# SCH.net
KiCad netlist of a schematic drawn in EAGLE
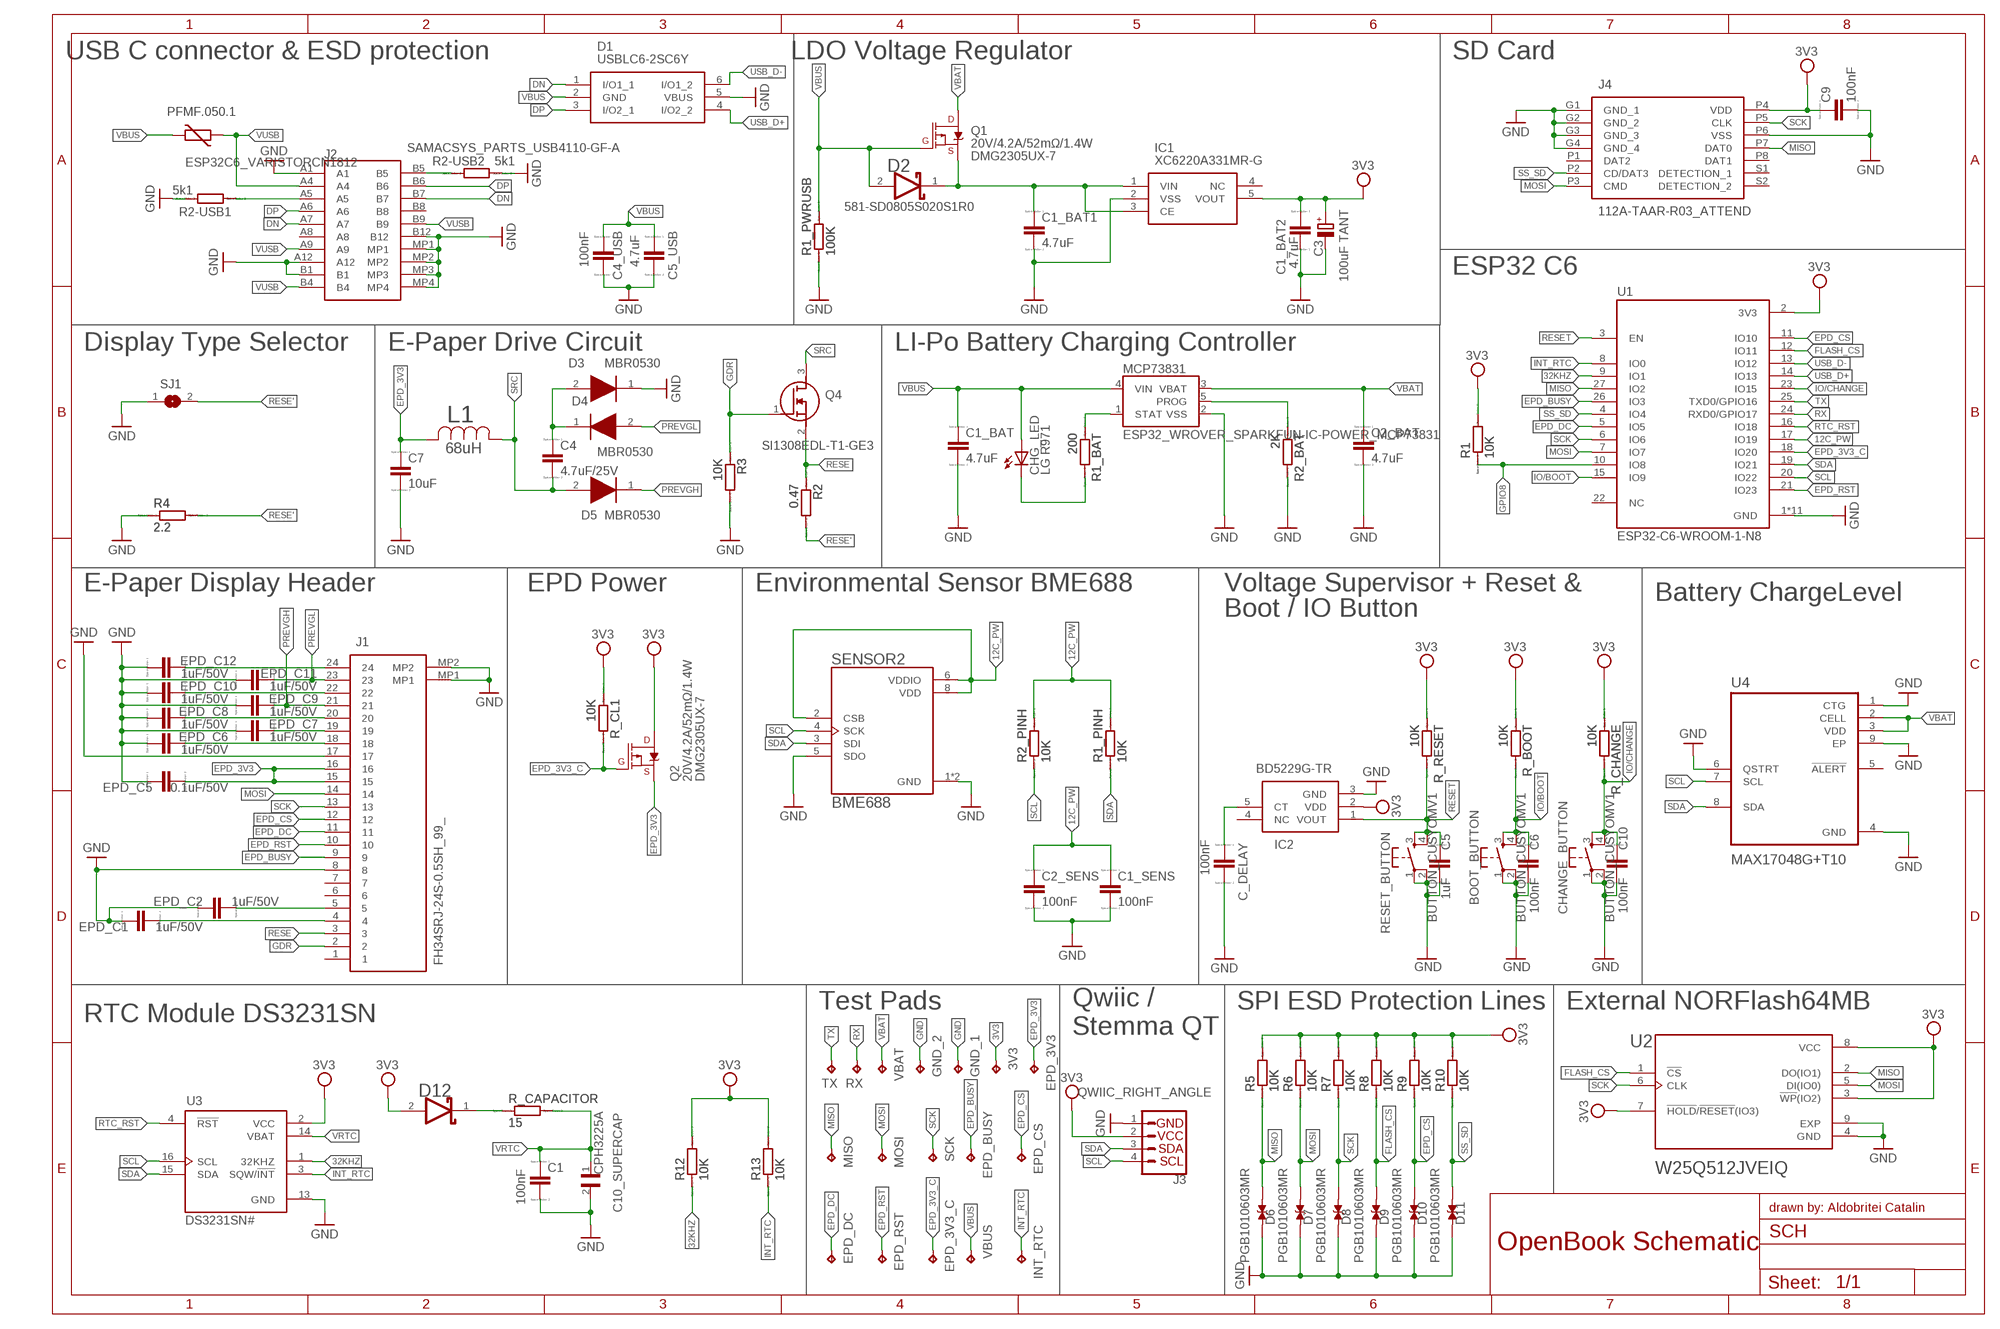
[diagram p0: schematic, sheet 1]

(export (version "E")
  (design (tool "Eeschema 10.0.6"))
  (components
    (comp (ref "3V3")
      (value "TPTP20R")
      (footprint "eagle-import:TP20R")
      (libsource (lib "eagle-import") (part "TPTP20R"))
    )
    (comp (ref "BOOT_BUTTON")
      (value "BUTTON_CUSYOMV1")
      (footprint "eagle-import:MYBUTTON")
      (libsource (lib "eagle-import") (part "BUTTON_CUSYOMV1"))
    )
    (comp (ref "C1")
      (value "100nF")
      (footprint "eagle-import:EAGLE-LTSPICE_C0402")
      (libsource (lib "eagle-import") (part "EAGLE-LTSPICE_CC0402"))
    )
    (comp (ref "C1_BAT")
      (value "4.7uF")
      (footprint "eagle-import:EAGLE-LTSPICE_C0402")
      (libsource (lib "eagle-import") (part "EAGLE-LTSPICE_CC0402"))
    )
    (comp (ref "C1_BAT1")
      (value "4.7uF")
      (footprint "eagle-import:EAGLE-LTSPICE_C0402")
      (libsource (lib "eagle-import") (part "EAGLE-LTSPICE_CC0402"))
    )
    (comp (ref "C1_BAT2")
      (value "4.7uF")
      (footprint "eagle-import:EAGLE-LTSPICE_C0402")
      (libsource (lib "eagle-import") (part "EAGLE-LTSPICE_CC0402"))
    )
    (comp (ref "C1_SENS")
      (value "100nF")
      (footprint "eagle-import:EAGLE-LTSPICE_C0402")
      (libsource (lib "eagle-import") (part "EAGLE-LTSPICE_CC0402"))
    )
    (comp (ref "C2_BAT")
      (value "4.7uF")
      (footprint "eagle-import:EAGLE-LTSPICE_C0402")
      (libsource (lib "eagle-import") (part "EAGLE-LTSPICE_CC0402"))
    )
    (comp (ref "C2_SENS")
      (value "100nF")
      (footprint "eagle-import:EAGLE-LTSPICE_C0402")
      (libsource (lib "eagle-import") (part "EAGLE-LTSPICE_CC0402"))
    )
    (comp (ref "C3")
      (value "100uF TANT")
      (footprint "eagle-import:RCL_CT3528")
      (libsource (lib "eagle-import") (part "RCL_CPOL-EUCT3528"))
    )
    (comp (ref "C4")
      (value "4.7uF/25V")
      (footprint "eagle-import:EAGLE-LTSPICE_C0402")
      (libsource (lib "eagle-import") (part "EAGLE-LTSPICE_CC0402"))
    )
    (comp (ref "C4_USB")
      (value "100nF")
      (footprint "eagle-import:EAGLE-LTSPICE_C0402")
      (libsource (lib "eagle-import") (part "EAGLE-LTSPICE_CC0402"))
    )
    (comp (ref "C5")
      (value "1uF")
      (footprint "eagle-import:EAGLE-LTSPICE_C0402")
      (libsource (lib "eagle-import") (part "EAGLE-LTSPICE_CC0402"))
    )
    (comp (ref "C5_USB")
      (value "4.7uF")
      (footprint "eagle-import:EAGLE-LTSPICE_C0402")
      (libsource (lib "eagle-import") (part "EAGLE-LTSPICE_CC0402"))
    )
    (comp (ref "C6")
      (value "100nF")
      (footprint "eagle-import:EAGLE-LTSPICE_C0402")
      (libsource (lib "eagle-import") (part "EAGLE-LTSPICE_CC0402"))
    )
    (comp (ref "C7")
      (value "10uF")
      (footprint "eagle-import:EAGLE-LTSPICE_C0402")
      (libsource (lib "eagle-import") (part "EAGLE-LTSPICE_CC0402"))
    )
    (comp (ref "C9")
      (value "100nF")
      (footprint "eagle-import:EAGLE-LTSPICE_C0402")
      (libsource (lib "eagle-import") (part "EAGLE-LTSPICE_CC0402"))
    )
    (comp (ref "C10")
      (value "100nF")
      (footprint "eagle-import:EAGLE-LTSPICE_C0402")
      (libsource (lib "eagle-import") (part "EAGLE-LTSPICE_CC0402"))
    )
    (comp (ref "C10_SUPERCAP")
      (value "CPH3225A")
      (footprint "eagle-import:CAPCP3225X100N")
      (fields (field (name "MF") "Seiko Instruments"))
      (libsource (lib "eagle-import") (part "CPH3225A"))
    )
    (comp (ref "CHANGE_BUTTON")
      (value "BUTTON_CUSYOMV1")
      (footprint "eagle-import:MYBUTTON")
      (libsource (lib "eagle-import") (part "BUTTON_CUSYOMV1"))
    )
    (comp (ref "CHG_LED")
      (value "LG R971")
      (footprint "eagle-import:ADAFRUIT_CHIP-LED0603")
      (libsource (lib "eagle-import") (part "ADAFRUIT_LEDCHIP-LED0603"))
    )
    (comp (ref "C_DELAY")
      (value "100nF")
      (footprint "eagle-import:EAGLE-LTSPICE_C0402")
      (libsource (lib "eagle-import") (part "EAGLE-LTSPICE_CC0402"))
    )
    (comp (ref "D1")
      (value "USBLC6-2SC6Y")
      (footprint "eagle-import:SOT95P280X145-6N")
      (fields (field (name "MF") "STMicroelectronics"))
      (libsource (lib "eagle-import") (part "USBLC6-2SC6Y"))
    )
    (comp (ref "D2")
      (value "ESP32_WROVER_AVX---SD0805S020S1R0_AVX_SD0805S020S1R0_0_0AVX_SD0805S020S1R0_0_0")
      (footprint "eagle-import:ESP32_WROVER_AVX---SD0805S020S1R0_AVX_SD0805S020S1R0_0")
      (fields
        (field (name "DIGIKEY_PART_NUMBER") "478-7800-1-ND")
        (field (name "MF") "AVX")
        (field (name "MOUSER_PART_NUMBER") "581-SD0805S020S1R0")
      )
      (libsource (lib "eagle-import") (part "ESP32_WROVER_AVX---SD0805S020S1R0_AVX_SD0805S020S1R0_0_0AVX_SD0805S020S1R0_0_0"))
    )
    (comp (ref "D3")
      (value "MBR0530")
      (footprint "eagle-import:SOD3716X135N")
      (fields (field (name "MF") "ON Semiconductor"))
      (libsource (lib "eagle-import") (part "MBR0530"))
    )
    (comp (ref "D4")
      (value "MBR0530")
      (footprint "eagle-import:SOD3716X135N")
      (fields (field (name "MF") "ON Semiconductor"))
      (libsource (lib "eagle-import") (part "MBR0530"))
    )
    (comp (ref "D5")
      (value "MBR0530")
      (footprint "eagle-import:SOD3716X135N")
      (fields (field (name "MF") "ON Semiconductor"))
      (libsource (lib "eagle-import") (part "MBR0530"))
    )
    (comp (ref "D6")
      (value "PGB1010603MR")
      (footprint "eagle-import:DIOC1608X36N")
      (fields (field (name "MF") "Littelfuse Inc."))
      (libsource (lib "eagle-import") (part "PGB1010603MR"))
    )
    (comp (ref "D7")
      (value "PGB1010603MR")
      (footprint "eagle-import:DIOC1608X36N")
      (fields (field (name "MF") "Littelfuse Inc."))
      (libsource (lib "eagle-import") (part "PGB1010603MR"))
    )
    (comp (ref "D8")
      (value "PGB1010603MR")
      (footprint "eagle-import:DIOC1608X36N")
      (fields (field (name "MF") "Littelfuse Inc."))
      (libsource (lib "eagle-import") (part "PGB1010603MR"))
    )
    (comp (ref "D9")
      (value "PGB1010603MR")
      (footprint "eagle-import:DIOC1608X36N")
      (fields (field (name "MF") "Littelfuse Inc."))
      (libsource (lib "eagle-import") (part "PGB1010603MR"))
    )
    (comp (ref "D10")
      (value "PGB1010603MR")
      (footprint "eagle-import:DIOC1608X36N")
      (fields (field (name "MF") "Littelfuse Inc."))
      (libsource (lib "eagle-import") (part "PGB1010603MR"))
    )
    (comp (ref "D11")
      (value "PGB1010603MR")
      (footprint "eagle-import:DIOC1608X36N")
      (fields (field (name "MF") "Littelfuse Inc."))
      (libsource (lib "eagle-import") (part "PGB1010603MR"))
    )
    (comp (ref "D12")
      (value "ESP32_WROVER_AVX---SD0805S020S1R0_AVX_SD0805S020S1R0_0_0AVX_SD0805S020S1R0_0_0")
      (footprint "eagle-import:ESP32_WROVER_AVX---SD0805S020S1R0_AVX_SD0805S020S1R0_0")
      (fields
        (field (name "DIGIKEY_PART_NUMBER") "478-7800-1-ND")
        (field (name "MF") "AVX")
        (field (name "MOUSER_PART_NUMBER") "581-SD0805S020S1R0")
      )
      (libsource (lib "eagle-import") (part "ESP32_WROVER_AVX---SD0805S020S1R0_AVX_SD0805S020S1R0_0_0AVX_SD0805S020S1R0_0_0"))
    )
    (comp (ref "EPD_3V3")
      (value "TPTP20R")
      (footprint "eagle-import:TP20R")
      (libsource (lib "eagle-import") (part "TPTP20R"))
    )
    (comp (ref "EPD_3V3_C")
      (value "TPTP20R")
      (footprint "eagle-import:TP20R")
      (libsource (lib "eagle-import") (part "TPTP20R"))
    )
    (comp (ref "EPD_BUSY")
      (value "TPTP20R")
      (footprint "eagle-import:TP20R")
      (libsource (lib "eagle-import") (part "TPTP20R"))
    )
    (comp (ref "EPD_C1")
      (value "1uF/50V")
      (footprint "eagle-import:EAGLE-LTSPICE_C0402")
      (libsource (lib "eagle-import") (part "EAGLE-LTSPICE_CC0402"))
    )
    (comp (ref "EPD_C2")
      (value "1uF/50V")
      (footprint "eagle-import:EAGLE-LTSPICE_C0402")
      (libsource (lib "eagle-import") (part "EAGLE-LTSPICE_CC0402"))
    )
    (comp (ref "EPD_C5")
      (value "0.1uF/50V")
      (footprint "eagle-import:EAGLE-LTSPICE_C0402")
      (libsource (lib "eagle-import") (part "EAGLE-LTSPICE_CC0402"))
    )
    (comp (ref "EPD_C6")
      (value "1uF/50V")
      (footprint "eagle-import:EAGLE-LTSPICE_C0402")
      (libsource (lib "eagle-import") (part "EAGLE-LTSPICE_CC0402"))
    )
    (comp (ref "EPD_C7")
      (value "1uF/50V")
      (footprint "eagle-import:EAGLE-LTSPICE_C0402")
      (libsource (lib "eagle-import") (part "EAGLE-LTSPICE_CC0402"))
    )
    (comp (ref "EPD_C8")
      (value "1uF/50V")
      (footprint "eagle-import:EAGLE-LTSPICE_C0402")
      (libsource (lib "eagle-import") (part "EAGLE-LTSPICE_CC0402"))
    )
    (comp (ref "EPD_C9")
      (value "1uF/50V")
      (footprint "eagle-import:EAGLE-LTSPICE_C0402")
      (libsource (lib "eagle-import") (part "EAGLE-LTSPICE_CC0402"))
    )
    (comp (ref "EPD_C10")
      (value "1uF/50V")
      (footprint "eagle-import:EAGLE-LTSPICE_C0402")
      (libsource (lib "eagle-import") (part "EAGLE-LTSPICE_CC0402"))
    )
    (comp (ref "EPD_C11")
      (value "1uF/50V")
      (footprint "eagle-import:EAGLE-LTSPICE_C0402")
      (libsource (lib "eagle-import") (part "EAGLE-LTSPICE_CC0402"))
    )
    (comp (ref "EPD_C12")
      (value "1uF/50V")
      (footprint "eagle-import:EAGLE-LTSPICE_C0402")
      (libsource (lib "eagle-import") (part "EAGLE-LTSPICE_CC0402"))
    )
    (comp (ref "EPD_CS")
      (value "TPTP20R")
      (footprint "eagle-import:TP20R")
      (libsource (lib "eagle-import") (part "TPTP20R"))
    )
    (comp (ref "EPD_DC")
      (value "TPTP20R")
      (footprint "eagle-import:TP20R")
      (libsource (lib "eagle-import") (part "TPTP20R"))
    )
    (comp (ref "EPD_RST")
      (value "TPTP20R")
      (footprint "eagle-import:TP20R")
      (libsource (lib "eagle-import") (part "TPTP20R"))
    )
    (comp (ref "GND_1")
      (value "TPTP20R")
      (footprint "eagle-import:TP20R")
      (libsource (lib "eagle-import") (part "TPTP20R"))
    )
    (comp (ref "GND_2")
      (value "TPTP20R")
      (footprint "eagle-import:TP20R")
      (libsource (lib "eagle-import") (part "TPTP20R"))
    )
    (comp (ref "IC1")
      (value "XC6220A331MR-G")
      (footprint "eagle-import:SOT95P280X120-5N")
      (fields (field (name "MOUSER_PART_NUMBER") "865-XC6220A331MR-G"))
      (libsource (lib "eagle-import") (part "XC6220A331MR-G"))
    )
    (comp (ref "IC2")
      (value "BD5229G-TR")
      (footprint "eagle-import:SOT95P280X125-5N")
      (fields (field (name "MOUSER_PART_NUMBER") "755-BD5229G-TR"))
      (libsource (lib "eagle-import") (part "BD5229G-TR"))
    )
    (comp (ref "INT_RTC")
      (value "TPTP20R")
      (footprint "eagle-import:TP20R")
      (libsource (lib "eagle-import") (part "TPTP20R"))
    )
    (comp (ref "J1")
      (value "FH34SRJ-24S-0.5SH_99_")
      (footprint "eagle-import:FH34SRJ24S05SH99")
      (fields
        (field (name "MANUFACTURER_PART_NUMBER") "FH34SRJ-24S-0.5SH(99)")
        (field (name "MOUSER_PART_NUMBER") "798-FH34SRJ24S05SH99")
      )
      (libsource (lib "eagle-import") (part "FH34SRJ-24S-0.5SH_99_"))
    )
    (comp (ref "J2")
      (value "SAMACSYS_PARTS_USB4110-GF-A")
      (footprint "eagle-import:SAMACSYS_PARTS_USB4110GFA")
      (fields
        (field (name "MANUFACTURER_PART_NUMBER") "USB4110-GF-A")
        (field (name "MOUSER_PART_NUMBER") "640-USB4110-GF-A")
      )
      (libsource (lib "eagle-import") (part "SAMACSYS_PARTS_USB4110-GF-A"))
    )
    (comp (ref "J3")
      (value "QWIIC_RIGHT_ANGLE")
      (footprint "eagle-import:JST04_1MM_RA")
      (libsource (lib "eagle-import") (part "QWIIC_CONNECTORJS-1MM"))
    )
    (comp (ref "J4")
      (value "112A-TAAR-R03_ATTEND")
      (footprint "eagle-import:112ATAARR03ATTEND")
      (fields (field (name "MANUFACTURER_PART_NUMBER") "112A-TAAR-R03 ATTEND"))
      (libsource (lib "eagle-import") (part "112A-TAAR-R03_ATTEND"))
    )
    (comp (ref "L1")
      (value "68uH")
      (footprint "eagle-import:IND_4828-WE-TPC_WRE")
      (fields
        (field (name "MANUFACTURER_PART_NUMBER") "744043680")
        (field (name "COPYRIGHT") "Copyright (C) 2024 Ultra Librarian. All rights reserved.")
      )
      (libsource (lib "eagle-import") (part "744043680IND_4828-WE-TPC_WRE"))
    )
    (comp (ref "MCP73831")
      (value "ESP32_WROVER_SPARKFUN-IC-POWER_MCP73831")
      (footprint "eagle-import:ESP32_WROVER_SPARKFUN-IC-POWER_SOT23-5")
      (libsource (lib "eagle-import") (part "ESP32_WROVER_SPARKFUN-IC-POWER_MCP73831"))
    )
    (comp (ref "MISO")
      (value "TPTP20R")
      (footprint "eagle-import:TP20R")
      (libsource (lib "eagle-import") (part "TPTP20R"))
    )
    (comp (ref "MOSI")
      (value "TPTP20R")
      (footprint "eagle-import:TP20R")
      (libsource (lib "eagle-import") (part "TPTP20R"))
    )
    (comp (ref "PFMF.050.1")
      (value "ESP32C6_VARISTORCN1812")
      (footprint "eagle-import:ESP32C6_VARISTOR_CT_CN1812")
      (libsource (lib "eagle-import") (part "ESP32C6_VARISTORCN1812"))
    )
    (comp (ref "Q1")
      (value "20V/4.2A/52mΩ/1.4W")
      (footprint "eagle-import:ESP32_WROVER_SPARKFUN-DISCRETESEMI_SOT23-3")
      (fields (field (name "PROD_ID") "DMG2305UX-7"))
      (libsource (lib "eagle-import") (part "ESP32_WROVER_SPARKFUN-DISCRETESEMI_MOSFET_PCH-DMG2305UX-7"))
    )
    (comp (ref "Q2")
      (value "20V/4.2A/52mΩ/1.4W")
      (footprint "eagle-import:ESP32_WROVER_SPARKFUN-DISCRETESEMI_SOT23-3")
      (fields (field (name "PROD_ID") "DMG2305UX-7"))
      (libsource (lib "eagle-import") (part "ESP32_WROVER_SPARKFUN-DISCRETESEMI_MOSFET_PCH-DMG2305UX-7"))
    )
    (comp (ref "Q4")
      (value "SI1308EDL-T1-GE3")
      (footprint "eagle-import:SOT65P210X110-3N")
      (fields (field (name "MF") "Vishay Siliconix"))
      (libsource (lib "eagle-import") (part "SI1308EDL-T1-GE3"))
    )
    (comp (ref "R1")
      (value "10K")
      (footprint "eagle-import:ESP32_WROVER_EAGLE-LTSPICE_R0402")
      (libsource (lib "eagle-import") (part "ESP32_WROVER_EAGLE-LTSPICE_RR0402"))
    )
    (comp (ref "R1_BAT")
      (value "200")
      (footprint "eagle-import:ESP32_WROVER_EAGLE-LTSPICE_R0402")
      (libsource (lib "eagle-import") (part "ESP32_WROVER_EAGLE-LTSPICE_RR0402"))
    )
    (comp (ref "R1_PINH")
      (value "10K")
      (footprint "eagle-import:ESP32_WROVER_EAGLE-LTSPICE_R0402")
      (libsource (lib "eagle-import") (part "ESP32_WROVER_EAGLE-LTSPICE_RR0402"))
    )
    (comp (ref "R1_PWRUSB")
      (value "100K")
      (footprint "eagle-import:ESP32_WROVER_EAGLE-LTSPICE_R0402")
      (libsource (lib "eagle-import") (part "ESP32_WROVER_EAGLE-LTSPICE_RR0402"))
    )
    (comp (ref "R2")
      (value "0.47")
      (footprint "eagle-import:ESP32_WROVER_EAGLE-LTSPICE_R0402")
      (libsource (lib "eagle-import") (part "ESP32_WROVER_EAGLE-LTSPICE_RR0402"))
    )
    (comp (ref "R2-USB1")
      (value "5k1")
      (footprint "eagle-import:ESP32_WROVER_EAGLE-LTSPICE_R0402")
      (libsource (lib "eagle-import") (part "ESP32_WROVER_EAGLE-LTSPICE_RR0402"))
    )
    (comp (ref "R2-USB2")
      (value "5k1")
      (footprint "eagle-import:ESP32_WROVER_EAGLE-LTSPICE_R0402")
      (libsource (lib "eagle-import") (part "ESP32_WROVER_EAGLE-LTSPICE_RR0402"))
    )
    (comp (ref "R2_BAT")
      (value "2K")
      (footprint "eagle-import:ESP32_WROVER_EAGLE-LTSPICE_R0402")
      (libsource (lib "eagle-import") (part "ESP32_WROVER_EAGLE-LTSPICE_RR0402"))
    )
    (comp (ref "R2_PINH")
      (value "10K")
      (footprint "eagle-import:ESP32_WROVER_EAGLE-LTSPICE_R0402")
      (libsource (lib "eagle-import") (part "ESP32_WROVER_EAGLE-LTSPICE_RR0402"))
    )
    (comp (ref "R3")
      (value "10K")
      (footprint "eagle-import:ESP32_WROVER_EAGLE-LTSPICE_R0402")
      (libsource (lib "eagle-import") (part "ESP32_WROVER_EAGLE-LTSPICE_RR0402"))
    )
    (comp (ref "R4")
      (value "2.2")
      (footprint "eagle-import:ESP32_WROVER_EAGLE-LTSPICE_R0402")
      (libsource (lib "eagle-import") (part "ESP32_WROVER_EAGLE-LTSPICE_RR0402"))
    )
    (comp (ref "R5")
      (value "10K")
      (footprint "eagle-import:ESP32_WROVER_EAGLE-LTSPICE_R0402")
      (libsource (lib "eagle-import") (part "ESP32_WROVER_EAGLE-LTSPICE_RR0402"))
    )
    (comp (ref "R6")
      (value "10K")
      (footprint "eagle-import:ESP32_WROVER_EAGLE-LTSPICE_R0402")
      (libsource (lib "eagle-import") (part "ESP32_WROVER_EAGLE-LTSPICE_RR0402"))
    )
    (comp (ref "R7")
      (value "10K")
      (footprint "eagle-import:ESP32_WROVER_EAGLE-LTSPICE_R0402")
      (libsource (lib "eagle-import") (part "ESP32_WROVER_EAGLE-LTSPICE_RR0402"))
    )
    (comp (ref "R8")
      (value "10K")
      (footprint "eagle-import:ESP32_WROVER_EAGLE-LTSPICE_R0402")
      (libsource (lib "eagle-import") (part "ESP32_WROVER_EAGLE-LTSPICE_RR0402"))
    )
    (comp (ref "R9")
      (value "10K")
      (footprint "eagle-import:ESP32_WROVER_EAGLE-LTSPICE_R0402")
      (libsource (lib "eagle-import") (part "ESP32_WROVER_EAGLE-LTSPICE_RR0402"))
    )
    (comp (ref "R10")
      (value "10K")
      (footprint "eagle-import:ESP32_WROVER_EAGLE-LTSPICE_R0402")
      (libsource (lib "eagle-import") (part "ESP32_WROVER_EAGLE-LTSPICE_RR0402"))
    )
    (comp (ref "R12")
      (value "10K")
      (footprint "eagle-import:ESP32_WROVER_EAGLE-LTSPICE_R0402")
      (libsource (lib "eagle-import") (part "ESP32_WROVER_EAGLE-LTSPICE_RR0402"))
    )
    (comp (ref "R13")
      (value "10K")
      (footprint "eagle-import:ESP32_WROVER_EAGLE-LTSPICE_R0402")
      (libsource (lib "eagle-import") (part "ESP32_WROVER_EAGLE-LTSPICE_RR0402"))
    )
    (comp (ref "RESET_BUTTON")
      (value "BUTTON_CUSYOMV1")
      (footprint "eagle-import:MYBUTTON")
      (libsource (lib "eagle-import") (part "BUTTON_CUSYOMV1"))
    )
    (comp (ref "RX")
      (value "TPTP20R")
      (footprint "eagle-import:TP20R")
      (libsource (lib "eagle-import") (part "TPTP20R"))
    )
    (comp (ref "R_BOOT")
      (value "10K")
      (footprint "eagle-import:ESP32_WROVER_EAGLE-LTSPICE_R0402")
      (libsource (lib "eagle-import") (part "ESP32_WROVER_EAGLE-LTSPICE_RR0402"))
    )
    (comp (ref "R_CAPACITOR")
      (value "15")
      (footprint "eagle-import:ESP32_WROVER_EAGLE-LTSPICE_R0402")
      (libsource (lib "eagle-import") (part "ESP32_WROVER_EAGLE-LTSPICE_RR0402"))
    )
    (comp (ref "R_CHANGE")
      (value "10K")
      (footprint "eagle-import:ESP32_WROVER_EAGLE-LTSPICE_R0402")
      (libsource (lib "eagle-import") (part "ESP32_WROVER_EAGLE-LTSPICE_RR0402"))
    )
    (comp (ref "R_CL1")
      (value "10K")
      (footprint "eagle-import:ESP32_WROVER_EAGLE-LTSPICE_R0402")
      (libsource (lib "eagle-import") (part "ESP32_WROVER_EAGLE-LTSPICE_RR0402"))
    )
    (comp (ref "R_RESET")
      (value "10K")
      (footprint "eagle-import:ESP32_WROVER_EAGLE-LTSPICE_R0402")
      (libsource (lib "eagle-import") (part "ESP32_WROVER_EAGLE-LTSPICE_RR0402"))
    )
    (comp (ref "SCK")
      (value "TPTP20R")
      (footprint "eagle-import:TP20R")
      (libsource (lib "eagle-import") (part "TPTP20R"))
    )
    (comp (ref "SENSOR2")
      (value "BME688")
      (footprint "eagle-import:ESP32_WROVER_BME680_PSON80P300X300X100-8N")
      (fields (field (name "MF") "Bosch Sensortec") (field (name "MP") "BME680"))
      (libsource (lib "eagle-import") (part "ESP32_WROVER_BME680_BME680"))
    )
    (comp (ref "SJ1") (value "SJ") (footprint "eagle-import:SJ") (libsource (lib "eagle-import") (part "SJ")))
    (comp (ref "TX")
      (value "TPTP20R")
      (footprint "eagle-import:TP20R")
      (libsource (lib "eagle-import") (part "TPTP20R"))
    )
    (comp (ref "U1")
      (value "ESP32-C6-WROOM-1-N8")
      (footprint "eagle-import:XCVR_ESP32-C6-WROOM-1-N8")
      (fields (field (name "MF") "Espressif Systems"))
      (libsource (lib "eagle-import") (part "ESP32-C6-WROOM-1-N8"))
    )
    (comp (ref "U2")
      (value "W25Q512JVEIQ")
      (footprint "eagle-import:SON127P600X800X80-9N")
      (fields (field (name "MF") "Winbond Electronics"))
      (libsource (lib "eagle-import") (part "W25Q512JVEIQ"))
    )
    (comp (ref "U3")
      (value "DS3231SN#")
      (footprint "eagle-import:SOIC127P1032X265-16N")
      (fields (field (name "MF") "Analog Devices"))
      (libsource (lib "eagle-import") (part "DS3231SN#"))
    )
    (comp (ref "U4")
      (value "MAX17048G+T10")
      (footprint "eagle-import:SON50P200X200X80-9N")
      (fields (field (name "MF") "Analog Devices"))
      (libsource (lib "eagle-import") (part "MAX17048G+T10"))
    )
    (comp (ref "VBAT")
      (value "TPTP20R")
      (footprint "eagle-import:TP20R")
      (libsource (lib "eagle-import") (part "TPTP20R"))
    )
    (comp (ref "VBUS")
      (value "TPTP20R")
      (footprint "eagle-import:TP20R")
      (libsource (lib "eagle-import") (part "TPTP20R"))
    )
  )
  (nets
    (net (code "1") (name "3V3") (class "Default")
      (node (ref "3V3") (pin "TP") (pinfunction "TP_TP") (pintype "input"))
      (node (ref "C1_BAT2") (pin "2") (pinfunction "2_2") (pintype "passive"))
      (node (ref "C3") (pin "+") (pinfunction "+_+") (pintype "passive"))
      (node (ref "C9") (pin "1") (pinfunction "1_1") (pintype "passive"))
      (node (ref "D12") (pin "2") (pinfunction "ANODE_2") (pintype "bidirectional"))
      (node (ref "IC1") (pin "5") (pinfunction "VOUT_5") (pintype "bidirectional"))
      (node (ref "IC2") (pin "2") (pinfunction "VDD_2") (pintype "bidirectional"))
      (node (ref "J3") (pin "2") (pinfunction "2_2") (pintype "power_in"))
      (node (ref "J4") (pin "P4") (pinfunction "VDD_P4") (pintype "bidirectional"))
      (node (ref "Q2") (pin "3") (pinfunction "D_3") (pintype "bidirectional"))
      (node (ref "R1") (pin "2") (pinfunction "2_2") (pintype "passive"))
      (node (ref "R10") (pin "2") (pinfunction "2_2") (pintype "passive"))
      (node (ref "R12") (pin "2") (pinfunction "2_2") (pintype "passive"))
      (node (ref "R13") (pin "2") (pinfunction "2_2") (pintype "passive"))
      (node (ref "R5") (pin "2") (pinfunction "2_2") (pintype "passive"))
      (node (ref "R6") (pin "2") (pinfunction "2_2") (pintype "passive"))
      (node (ref "R7") (pin "2") (pinfunction "2_2") (pintype "passive"))
      (node (ref "R8") (pin "2") (pinfunction "2_2") (pintype "passive"))
      (node (ref "R9") (pin "2") (pinfunction "2_2") (pintype "passive"))
      (node (ref "R_BOOT") (pin "1") (pinfunction "1_1") (pintype "passive"))
      (node (ref "R_CHANGE") (pin "1") (pinfunction "1_1") (pintype "passive"))
      (node (ref "R_CL1") (pin "1") (pinfunction "1_1") (pintype "passive"))
      (node (ref "R_RESET") (pin "1") (pinfunction "1_1") (pintype "passive"))
      (node (ref "U1") (pin "2") (pinfunction "3V3_2") (pintype "power_in"))
      (node (ref "U2") (pin "3") (pinfunction "~{WP}(IO2)_3") (pintype "bidirectional"))
      (node (ref "U2") (pin "7") (pinfunction "~{HOLD}/~{RESET}(IO3)_7") (pintype "bidirectional"))
      (node (ref "U2") (pin "8") (pinfunction "VCC_8") (pintype "power_in"))
      (node (ref "U3") (pin "2") (pinfunction "VCC_2") (pintype "power_in"))
    )
    (net (code "2") (name "12C_PW") (class "Default")
      (node (ref "C1_SENS") (pin "1") (pinfunction "1_1") (pintype "passive"))
      (node (ref "C2_SENS") (pin "1") (pinfunction "1_1") (pintype "passive"))
      (node (ref "R1_PINH") (pin "2") (pinfunction "2_2") (pintype "passive"))
      (node (ref "R2_PINH") (pin "2") (pinfunction "2_2") (pintype "passive"))
      (node (ref "SENSOR2") (pin "2") (pinfunction "CSB_2") (pintype "input"))
      (node (ref "SENSOR2") (pin "6") (pinfunction "VDDIO_6") (pintype "power_in"))
      (node (ref "SENSOR2") (pin "8") (pinfunction "VDD_8") (pintype "power_in"))
      (node (ref "U1") (pin "17") (pinfunction "IO19_17") (pintype "bidirectional"))
    )
    (net (code "3") (name "32KHZ") (class "Default")
      (node (ref "R12") (pin "1") (pinfunction "1_1") (pintype "passive"))
      (node (ref "U1") (pin "9") (pinfunction "IO1_9") (pintype "bidirectional"))
      (node (ref "U3") (pin "1") (pinfunction "32KHZ_1") (pintype "output"))
    )
    (net (code "4") (name "DN") (class "Default")
      (node (ref "D1") (pin "1") (pinfunction "I/O1_1_1") (pintype "bidirectional"))
      (node (ref "J2") (pin "A7") (pinfunction "A7_A7") (pintype "bidirectional"))
      (node (ref "J2") (pin "B7") (pinfunction "B7_B7") (pintype "bidirectional"))
    )
    (net (code "5") (name "DP") (class "Default")
      (node (ref "D1") (pin "3") (pinfunction "I/O2_1_3") (pintype "bidirectional"))
      (node (ref "J2") (pin "A6") (pinfunction "A6_A6") (pintype "bidirectional"))
      (node (ref "J2") (pin "B6") (pinfunction "B6_B6") (pintype "bidirectional"))
    )
    (net (code "6") (name "EPD_3V3") (class "Default")
      (node (ref "C7") (pin "1") (pinfunction "1_1") (pintype "passive"))
      (node (ref "EPD_3V3") (pin "TP") (pinfunction "TP_TP") (pintype "input"))
      (node (ref "EPD_C5") (pin "2") (pinfunction "2_2") (pintype "passive"))
      (node (ref "J1") (pin "15") (pinfunction "15_15") (pintype "bidirectional"))
      (node (ref "J1") (pin "16") (pinfunction "16_16") (pintype "bidirectional"))
      (node (ref "L1") (pin "2") (pinfunction "2_2") (pintype "passive"))
      (node (ref "Q2") (pin "2") (pinfunction "S_2") (pintype "bidirectional"))
    )
    (net (code "7") (name "EPD_3V3_C") (class "Default")
      (node (ref "EPD_3V3_C") (pin "TP") (pinfunction "TP_TP") (pintype "input"))
      (node (ref "Q2") (pin "1") (pinfunction "G_1") (pintype "bidirectional"))
      (node (ref "R_CL1") (pin "2") (pinfunction "2_2") (pintype "passive"))
      (node (ref "U1") (pin "18") (pinfunction "IO20_18") (pintype "bidirectional"))
    )
    (net (code "8") (name "EPD_BUSY") (class "Default")
      (node (ref "EPD_BUSY") (pin "TP") (pinfunction "TP_TP") (pintype "input"))
      (node (ref "J1") (pin "9") (pinfunction "9_9") (pintype "bidirectional"))
      (node (ref "U1") (pin "26") (pinfunction "IO3_26") (pintype "bidirectional"))
    )
    (net (code "9") (name "EPD_CS") (class "Default")
      (node (ref "D10") (pin "2") (pinfunction "2_2") (pintype "passive"))
      (node (ref "EPD_CS") (pin "TP") (pinfunction "TP_TP") (pintype "input"))
      (node (ref "J1") (pin "12") (pinfunction "12_12") (pintype "bidirectional"))
      (node (ref "R9") (pin "1") (pinfunction "1_1") (pintype "passive"))
      (node (ref "U1") (pin "11") (pinfunction "IO10_11") (pintype "bidirectional"))
    )
    (net (code "10") (name "EPD_DC") (class "Default")
      (node (ref "EPD_DC") (pin "TP") (pinfunction "TP_TP") (pintype "input"))
      (node (ref "J1") (pin "11") (pinfunction "11_11") (pintype "bidirectional"))
      (node (ref "U1") (pin "5") (pinfunction "IO5_5") (pintype "bidirectional"))
    )
    (net (code "11") (name "EPD_RST") (class "Default")
      (node (ref "EPD_RST") (pin "TP") (pinfunction "TP_TP") (pintype "input"))
      (node (ref "J1") (pin "10") (pinfunction "10_10") (pintype "bidirectional"))
      (node (ref "U1") (pin "21") (pinfunction "IO23_21") (pintype "bidirectional"))
    )
    (net (code "12") (name "FLASH_CS") (class "Default")
      (node (ref "D9") (pin "2") (pinfunction "2_2") (pintype "passive"))
      (node (ref "R8") (pin "1") (pinfunction "1_1") (pintype "passive"))
      (node (ref "U1") (pin "12") (pinfunction "IO11_12") (pintype "bidirectional"))
      (node (ref "U2") (pin "1") (pinfunction "~{CS}_1") (pintype "input"))
    )
    (net (code "13") (name "GDR") (class "Default")
      (node (ref "J1") (pin "2") (pinfunction "2_2") (pintype "bidirectional"))
      (node (ref "Q4") (pin "1") (pinfunction "G_1") (pintype "bidirectional"))
      (node (ref "R3") (pin "1") (pinfunction "1_1") (pintype "passive"))
    )
    (net (code "14") (name "GND") (class "Default")
      (node (ref "BOOT_BUTTON") (pin "1") (pinfunction "1_1") (pintype "passive"))
      (node (ref "BOOT_BUTTON") (pin "2") (pinfunction "2_2") (pintype "passive"))
      (node (ref "C1") (pin "2") (pinfunction "2_2") (pintype "passive"))
      (node (ref "C10") (pin "2") (pinfunction "2_2") (pintype "passive"))
      (node (ref "C10_SUPERCAP") (pin "2") (pinfunction "2_2") (pintype "passive"))
      (node (ref "C1_BAT") (pin "2") (pinfunction "2_2") (pintype "passive"))
      (node (ref "C1_BAT1") (pin "2") (pinfunction "2_2") (pintype "passive"))
      (node (ref "C1_BAT2") (pin "1") (pinfunction "1_1") (pintype "passive"))
      (node (ref "C1_SENS") (pin "2") (pinfunction "2_2") (pintype "passive"))
      (node (ref "C2_BAT") (pin "2") (pinfunction "2_2") (pintype "passive"))
      (node (ref "C2_SENS") (pin "2") (pinfunction "2_2") (pintype "passive"))
      (node (ref "C3") (pin "-") (pinfunction "-_-") (pintype "passive"))
      (node (ref "C4_USB") (pin "2") (pinfunction "2_2") (pintype "passive"))
      (node (ref "C5") (pin "2") (pinfunction "2_2") (pintype "passive"))
      (node (ref "C5_USB") (pin "2") (pinfunction "2_2") (pintype "passive"))
      (node (ref "C6") (pin "2") (pinfunction "2_2") (pintype "passive"))
      (node (ref "C7") (pin "2") (pinfunction "2_2") (pintype "passive"))
      (node (ref "C9") (pin "2") (pinfunction "2_2") (pintype "passive"))
      (node (ref "CHANGE_BUTTON") (pin "1") (pinfunction "1_1") (pintype "passive"))
      (node (ref "CHANGE_BUTTON") (pin "2") (pinfunction "2_2") (pintype "passive"))
      (node (ref "C_DELAY") (pin "2") (pinfunction "2_2") (pintype "passive"))
      (node (ref "D1") (pin "5") (pinfunction "VBUS_5") (pintype "bidirectional"))
      (node (ref "D10") (pin "1") (pinfunction "1_1") (pintype "passive"))
      (node (ref "D11") (pin "1") (pinfunction "1_1") (pintype "passive"))
      (node (ref "D3") (pin "1") (pinfunction "K_1") (pintype "bidirectional"))
      (node (ref "D6") (pin "1") (pinfunction "1_1") (pintype "passive"))
      (node (ref "D7") (pin "1") (pinfunction "1_1") (pintype "passive"))
      (node (ref "D8") (pin "1") (pinfunction "1_1") (pintype "passive"))
      (node (ref "D9") (pin "1") (pinfunction "1_1") (pintype "passive"))
      (node (ref "EPD_C1") (pin "1") (pinfunction "1_1") (pintype "passive"))
      (node (ref "EPD_C10") (pin "1") (pinfunction "1_1") (pintype "passive"))
      (node (ref "EPD_C11") (pin "1") (pinfunction "1_1") (pintype "passive"))
      (node (ref "EPD_C12") (pin "1") (pinfunction "1_1") (pintype "passive"))
      (node (ref "EPD_C2") (pin "1") (pinfunction "1_1") (pintype "passive"))
      (node (ref "EPD_C5") (pin "1") (pinfunction "1_1") (pintype "passive"))
      (node (ref "EPD_C6") (pin "1") (pinfunction "1_1") (pintype "passive"))
      (node (ref "EPD_C7") (pin "1") (pinfunction "1_1") (pintype "passive"))
      (node (ref "EPD_C8") (pin "1") (pinfunction "1_1") (pintype "passive"))
      (node (ref "EPD_C9") (pin "1") (pinfunction "1_1") (pintype "passive"))
      (node (ref "GND_1") (pin "TP") (pinfunction "TP_TP") (pintype "input"))
      (node (ref "GND_2") (pin "TP") (pinfunction "TP_TP") (pintype "input"))
      (node (ref "IC1") (pin "2") (pinfunction "VSS_2") (pintype "bidirectional"))
      (node (ref "IC2") (pin "3") (pinfunction "GND_3") (pintype "bidirectional"))
      (node (ref "J1") (pin "17") (pinfunction "17_17") (pintype "bidirectional"))
      (node (ref "J1") (pin "8") (pinfunction "8_8") (pintype "bidirectional"))
      (node (ref "J1") (pin "MP1") (pinfunction "MP1_MP1") (pintype "bidirectional"))
      (node (ref "J1") (pin "MP2") (pinfunction "MP2_MP2") (pintype "bidirectional"))
      (node (ref "J2") (pin "A1") (pinfunction "A1_A1") (pintype "bidirectional"))
      (node (ref "J2") (pin "A12") (pinfunction "A12_A12") (pintype "bidirectional"))
      (node (ref "J2") (pin "B1") (pinfunction "B1_B1") (pintype "bidirectional"))
      (node (ref "J2") (pin "B12") (pinfunction "B12_B12") (pintype "bidirectional"))
      (node (ref "J2") (pin "MP1") (pinfunction "MP1_MP1") (pintype "bidirectional"))
      (node (ref "J2") (pin "MP2") (pinfunction "MP2_MP2") (pintype "bidirectional"))
      (node (ref "J2") (pin "MP3") (pinfunction "MP3_MP3") (pintype "bidirectional"))
      (node (ref "J2") (pin "MP4") (pinfunction "MP4_MP4") (pintype "bidirectional"))
      (node (ref "J3") (pin "1") (pinfunction "1_1") (pintype "power_in"))
      (node (ref "J4") (pin "G1") (pinfunction "GND_1_G1") (pintype "bidirectional"))
      (node (ref "J4") (pin "G2") (pinfunction "GND_2_G2") (pintype "bidirectional"))
      (node (ref "J4") (pin "G3") (pinfunction "GND_3_G3") (pintype "bidirectional"))
      (node (ref "J4") (pin "G4") (pinfunction "GND_4_G4") (pintype "bidirectional"))
      (node (ref "J4") (pin "P6") (pinfunction "VSS_P6") (pintype "bidirectional"))
      (node (ref "MCP73831") (pin "2") (pinfunction "VSS_2") (pintype "power_in"))
      (node (ref "R1_PWRUSB") (pin "1") (pinfunction "1_1") (pintype "passive"))
      (node (ref "R2-USB1") (pin "1") (pinfunction "1_1") (pintype "passive"))
      (node (ref "R2-USB2") (pin "2") (pinfunction "2_2") (pintype "passive"))
      (node (ref "R2_BAT") (pin "2") (pinfunction "2_2") (pintype "passive"))
      (node (ref "R3") (pin "2") (pinfunction "2_2") (pintype "passive"))
      (node (ref "R4") (pin "1") (pinfunction "1_1") (pintype "passive"))
      (node (ref "RESET_BUTTON") (pin "1") (pinfunction "1_1") (pintype "passive"))
      (node (ref "RESET_BUTTON") (pin "2") (pinfunction "2_2") (pintype "passive"))
      (node (ref "SENSOR2") (pin "1") (pinfunction "GND_1") (pintype "power_in"))
      (node (ref "SENSOR2") (pin "5") (pinfunction "SDO_5") (pintype "bidirectional"))
      (node (ref "SENSOR2") (pin "7") (pinfunction "GND_7") (pintype "power_in"))
      (node (ref "SJ1") (pin "1") (pinfunction "1_1") (pintype "passive"))
      (node (ref "U1") (pin "1") (pinfunction "GND_1") (pintype "power_in"))
      (node (ref "U1") (pin "28") (pinfunction "GND_28") (pintype "power_in"))
      (node (ref "U1") (pin "29_1") (pinfunction "GND_29_1") (pintype "power_in"))
      (node (ref "U1") (pin "29_2") (pinfunction "GND_29_2") (pintype "power_in"))
      (node (ref "U1") (pin "29_3") (pinfunction "GND_29_3") (pintype "power_in"))
      (node (ref "U1") (pin "29_4") (pinfunction "GND_29_4") (pintype "power_in"))
      (node (ref "U1") (pin "29_5") (pinfunction "GND_29_5") (pintype "power_in"))
      (node (ref "U1") (pin "29_6") (pinfunction "GND_29_6") (pintype "power_in"))
      (node (ref "U1") (pin "29_7") (pinfunction "GND_29_7") (pintype "power_in"))
      (node (ref "U1") (pin "29_8") (pinfunction "GND_29_8") (pintype "power_in"))
      (node (ref "U1") (pin "29_9") (pinfunction "GND_29_9") (pintype "power_in"))
      (node (ref "U2") (pin "4") (pinfunction "GND_4") (pintype "power_in"))
      (node (ref "U2") (pin "9") (pinfunction "EXP_9") (pintype "passive"))
      (node (ref "U3") (pin "13") (pinfunction "GND_13") (pintype "power_in"))
      (node (ref "U4") (pin "1") (pinfunction "CTG_1") (pintype "power_in"))
      (node (ref "U4") (pin "4") (pinfunction "GND_4") (pintype "power_in"))
      (node (ref "U4") (pin "6") (pinfunction "QSTRT_6") (pintype "input"))
      (node (ref "U4") (pin "9") (pinfunction "EP_9") (pintype "power_in"))
    )
    (net (code "15") (name "GPIO8") (class "Default")
      (node (ref "R1") (pin "1") (pinfunction "1_1") (pintype "passive"))
      (node (ref "U1") (pin "10") (pinfunction "IO8_10") (pintype "bidirectional"))
    )
    (net (code "16") (name "INT_RTC") (class "Default")
      (node (ref "INT_RTC") (pin "TP") (pinfunction "TP_TP") (pintype "input"))
      (node (ref "R13") (pin "1") (pinfunction "1_1") (pintype "passive"))
      (node (ref "U1") (pin "8") (pinfunction "IO0_8") (pintype "bidirectional"))
      (node (ref "U3") (pin "3") (pinfunction "SQW/~{INT}_3") (pintype "output"))
    )
    (net (code "17") (name "IO{slash}BOOT") (class "Default")
      (node (ref "BOOT_BUTTON") (pin "3") (pinfunction "3_3") (pintype "passive"))
      (node (ref "BOOT_BUTTON") (pin "4") (pinfunction "4_4") (pintype "passive"))
      (node (ref "C6") (pin "1") (pinfunction "1_1") (pintype "passive"))
      (node (ref "R_BOOT") (pin "2") (pinfunction "2_2") (pintype "passive"))
      (node (ref "U1") (pin "15") (pinfunction "IO9_15") (pintype "bidirectional"))
    )
    (net (code "18") (name "IO{slash}CHANGE") (class "Default")
      (node (ref "C10") (pin "1") (pinfunction "1_1") (pintype "passive"))
      (node (ref "CHANGE_BUTTON") (pin "3") (pinfunction "3_3") (pintype "passive"))
      (node (ref "CHANGE_BUTTON") (pin "4") (pinfunction "4_4") (pintype "passive"))
      (node (ref "R_CHANGE") (pin "2") (pinfunction "2_2") (pintype "passive"))
      (node (ref "U1") (pin "23") (pinfunction "IO15_23") (pintype "bidirectional"))
    )
    (net (code "19") (name "MISO") (class "Default")
      (node (ref "D6") (pin "2") (pinfunction "2_2") (pintype "passive"))
      (node (ref "J4") (pin "P7") (pinfunction "DAT0_P7") (pintype "bidirectional"))
      (node (ref "MISO") (pin "TP") (pinfunction "TP_TP") (pintype "input"))
      (node (ref "R5") (pin "1") (pinfunction "1_1") (pintype "passive"))
      (node (ref "U1") (pin "27") (pinfunction "IO2_27") (pintype "bidirectional"))
      (node (ref "U2") (pin "2") (pinfunction "DO(IO1)_2") (pintype "bidirectional"))
    )
    (net (code "20") (name "MOSI") (class "Default")
      (node (ref "D7") (pin "2") (pinfunction "2_2") (pintype "passive"))
      (node (ref "J1") (pin "14") (pinfunction "14_14") (pintype "bidirectional"))
      (node (ref "J4") (pin "P3") (pinfunction "CMD_P3") (pintype "bidirectional"))
      (node (ref "MOSI") (pin "TP") (pinfunction "TP_TP") (pintype "input"))
      (node (ref "R6") (pin "1") (pinfunction "1_1") (pintype "passive"))
      (node (ref "U1") (pin "7") (pinfunction "IO7_7") (pintype "bidirectional"))
      (node (ref "U2") (pin "5") (pinfunction "DI(IO0)_5") (pintype "bidirectional"))
    )
    (net (code "21") (name "Net-(CHG_LED-PadC)") (class "Default")
      (node (ref "CHG_LED") (pin "C") (pinfunction "C_C") (pintype "passive"))
      (node (ref "R1_BAT") (pin "2") (pinfunction "2_2") (pintype "passive"))
    )
    (net (code "22") (name "Net-(D2-CATHODE)") (class "Default")
      (node (ref "C1_BAT1") (pin "1") (pinfunction "1_1") (pintype "passive"))
      (node (ref "D2") (pin "1") (pinfunction "CATHODE_1") (pintype "bidirectional"))
      (node (ref "IC1") (pin "1") (pinfunction "VIN_1") (pintype "bidirectional"))
      (node (ref "IC1") (pin "3") (pinfunction "CE_3") (pintype "bidirectional"))
      (node (ref "Q1") (pin "2") (pinfunction "S_2") (pintype "bidirectional"))
    )
    (net (code "23") (name "Net-(D3-A)") (class "Default")
      (node (ref "C4") (pin "1") (pinfunction "1_1") (pintype "passive"))
      (node (ref "D3") (pin "2") (pinfunction "A_2") (pintype "bidirectional"))
      (node (ref "D4") (pin "1") (pinfunction "K_1") (pintype "bidirectional"))
    )
    (net (code "24") (name "Net-(D12-CATHODE)") (class "Default")
      (node (ref "D12") (pin "1") (pinfunction "CATHODE_1") (pintype "bidirectional"))
      (node (ref "R_CAPACITOR") (pin "1") (pinfunction "1_1") (pintype "passive"))
    )
    (net (code "25") (name "Net-(EPD_C1-Pad2)") (class "Default")
      (node (ref "EPD_C1") (pin "2") (pinfunction "2_2") (pintype "passive"))
      (node (ref "J1") (pin "4") (pinfunction "4_4") (pintype "bidirectional"))
    )
    (net (code "26") (name "Net-(EPD_C2-Pad2)") (class "Default")
      (node (ref "EPD_C2") (pin "2") (pinfunction "2_2") (pintype "passive"))
      (node (ref "J1") (pin "5") (pinfunction "5_5") (pintype "bidirectional"))
    )
    (net (code "27") (name "Net-(EPD_C6-Pad2)") (class "Default")
      (node (ref "EPD_C6") (pin "2") (pinfunction "2_2") (pintype "passive"))
      (node (ref "J1") (pin "18") (pinfunction "18_18") (pintype "bidirectional"))
    )
    (net (code "28") (name "Net-(EPD_C7-Pad2)") (class "Default")
      (node (ref "EPD_C7") (pin "2") (pinfunction "2_2") (pintype "passive"))
      (node (ref "J1") (pin "19") (pinfunction "19_19") (pintype "bidirectional"))
    )
    (net (code "29") (name "Net-(EPD_C8-Pad2)") (class "Default")
      (node (ref "EPD_C8") (pin "2") (pinfunction "2_2") (pintype "passive"))
      (node (ref "J1") (pin "20") (pinfunction "20_20") (pintype "bidirectional"))
    )
    (net (code "30") (name "Net-(EPD_C10-Pad2)") (class "Default")
      (node (ref "EPD_C10") (pin "2") (pinfunction "2_2") (pintype "passive"))
      (node (ref "J1") (pin "22") (pinfunction "22_22") (pintype "bidirectional"))
    )
    (net (code "31") (name "Net-(EPD_C12-Pad2)") (class "Default")
      (node (ref "EPD_C12") (pin "2") (pinfunction "2_2") (pintype "passive"))
      (node (ref "J1") (pin "24") (pinfunction "24_24") (pintype "bidirectional"))
    )
    (net (code "32") (name "Net-(IC2-CT)") (class "Default")
      (node (ref "C_DELAY") (pin "1") (pinfunction "1_1") (pintype "passive"))
      (node (ref "IC2") (pin "5") (pinfunction "CT_5") (pintype "bidirectional"))
    )
    (net (code "33") (name "Net-(J2-PadA5)") (class "Default")
      (node (ref "J2") (pin "A5") (pinfunction "A5_A5") (pintype "bidirectional"))
      (node (ref "R2-USB1") (pin "2") (pinfunction "2_2") (pintype "passive"))
    )
    (net (code "34") (name "Net-(J2-PadB5)") (class "Default")
      (node (ref "J2") (pin "B5") (pinfunction "B5_B5") (pintype "bidirectional"))
      (node (ref "R2-USB2") (pin "1") (pinfunction "1_1") (pintype "passive"))
    )
    (net (code "35") (name "Net-(MCP73831-PROG)") (class "Default")
      (node (ref "MCP73831") (pin "5") (pinfunction "PROG_5") (pintype "input"))
      (node (ref "R2_BAT") (pin "1") (pinfunction "1_1") (pintype "passive"))
    )
    (net (code "36") (name "Net-(MCP73831-STAT)") (class "Default")
      (node (ref "MCP73831") (pin "1") (pinfunction "STAT_1") (pintype "output"))
      (node (ref "R1_BAT") (pin "1") (pinfunction "1_1") (pintype "passive"))
    )
    (net (code "37") (name "PREVGH") (class "Default")
      (node (ref "D5") (pin "1") (pinfunction "K_1") (pintype "bidirectional"))
      (node (ref "EPD_C9") (pin "2") (pinfunction "2_2") (pintype "passive"))
      (node (ref "J1") (pin "21") (pinfunction "21_21") (pintype "bidirectional"))
    )
    (net (code "38") (name "PREVGL") (class "Default")
      (node (ref "D4") (pin "2") (pinfunction "A_2") (pintype "bidirectional"))
      (node (ref "EPD_C11") (pin "2") (pinfunction "2_2") (pintype "passive"))
      (node (ref "J1") (pin "23") (pinfunction "23_23") (pintype "bidirectional"))
    )
    (net (code "39") (name "RESE") (class "Default")
      (node (ref "J1") (pin "3") (pinfunction "3_3") (pintype "bidirectional"))
      (node (ref "Q4") (pin "2") (pinfunction "S_2") (pintype "bidirectional"))
      (node (ref "R2") (pin "1") (pinfunction "1_1") (pintype "passive"))
    )
    (net (code "40") (name "RESE'") (class "Default")
      (node (ref "R2") (pin "2") (pinfunction "2_2") (pintype "passive"))
      (node (ref "R4") (pin "2") (pinfunction "2_2") (pintype "passive"))
      (node (ref "SJ1") (pin "2") (pinfunction "2_2") (pintype "passive"))
    )
    (net (code "41") (name "RESET") (class "Default")
      (node (ref "C5") (pin "1") (pinfunction "1_1") (pintype "passive"))
      (node (ref "IC2") (pin "1") (pinfunction "VOUT_1") (pintype "bidirectional"))
      (node (ref "RESET_BUTTON") (pin "3") (pinfunction "3_3") (pintype "passive"))
      (node (ref "RESET_BUTTON") (pin "4") (pinfunction "4_4") (pintype "passive"))
      (node (ref "R_RESET") (pin "2") (pinfunction "2_2") (pintype "passive"))
      (node (ref "U1") (pin "3") (pinfunction "EN_3") (pintype "input"))
    )
    (net (code "42") (name "RTC_RST") (class "Default")
      (node (ref "U1") (pin "16") (pinfunction "IO18_16") (pintype "bidirectional"))
      (node (ref "U3") (pin "4") (pinfunction "~{RST}_4") (pintype "input"))
    )
    (net (code "43") (name "RX") (class "Default")
      (node (ref "RX") (pin "TP") (pinfunction "TP_TP") (pintype "input"))
      (node (ref "U1") (pin "24") (pinfunction "RXD0/GPIO17_24") (pintype "bidirectional"))
    )
    (net (code "44") (name "SCK") (class "Default")
      (node (ref "D8") (pin "2") (pinfunction "2_2") (pintype "passive"))
      (node (ref "J1") (pin "13") (pinfunction "13_13") (pintype "bidirectional"))
      (node (ref "J4") (pin "P5") (pinfunction "CLK_P5") (pintype "bidirectional"))
      (node (ref "R7") (pin "1") (pinfunction "1_1") (pintype "passive"))
      (node (ref "SCK") (pin "TP") (pinfunction "TP_TP") (pintype "input"))
      (node (ref "U1") (pin "6") (pinfunction "IO6_6") (pintype "bidirectional"))
      (node (ref "U2") (pin "6") (pinfunction "CLK_6") (pintype "input"))
    )
    (net (code "45") (name "SCL") (class "Default")
      (node (ref "J3") (pin "4") (pinfunction "4_4") (pintype "passive"))
      (node (ref "R2_PINH") (pin "1") (pinfunction "1_1") (pintype "passive"))
      (node (ref "SENSOR2") (pin "4") (pinfunction "SCK_4") (pintype "input"))
      (node (ref "U1") (pin "20") (pinfunction "IO22_20") (pintype "bidirectional"))
      (node (ref "U3") (pin "16") (pinfunction "SCL_16") (pintype "input"))
      (node (ref "U4") (pin "7") (pinfunction "SCL_7") (pintype "input"))
    )
    (net (code "46") (name "SDA") (class "Default")
      (node (ref "J3") (pin "3") (pinfunction "3_3") (pintype "passive"))
      (node (ref "R1_PINH") (pin "1") (pinfunction "1_1") (pintype "passive"))
      (node (ref "SENSOR2") (pin "3") (pinfunction "SDI_3") (pintype "bidirectional"))
      (node (ref "U1") (pin "19") (pinfunction "IO21_19") (pintype "bidirectional"))
      (node (ref "U3") (pin "15") (pinfunction "SDA_15") (pintype "bidirectional"))
      (node (ref "U4") (pin "8") (pinfunction "SDA_8") (pintype "bidirectional"))
    )
    (net (code "47") (name "SRC") (class "Default")
      (node (ref "C4") (pin "2") (pinfunction "2_2") (pintype "passive"))
      (node (ref "D5") (pin "2") (pinfunction "A_2") (pintype "bidirectional"))
      (node (ref "L1") (pin "1") (pinfunction "1_1") (pintype "passive"))
      (node (ref "Q4") (pin "3") (pinfunction "D_3") (pintype "bidirectional"))
    )
    (net (code "48") (name "SS_SD") (class "Default")
      (node (ref "D11") (pin "2") (pinfunction "2_2") (pintype "passive"))
      (node (ref "J4") (pin "P2") (pinfunction "CD/DAT3_P2") (pintype "bidirectional"))
      (node (ref "R10") (pin "1") (pinfunction "1_1") (pintype "passive"))
      (node (ref "U1") (pin "4") (pinfunction "IO4_4") (pintype "bidirectional"))
    )
    (net (code "49") (name "TX") (class "Default")
      (node (ref "TX") (pin "TP") (pinfunction "TP_TP") (pintype "input"))
      (node (ref "U1") (pin "25") (pinfunction "TXD0/GPIO16_25") (pintype "bidirectional"))
    )
    (net (code "50") (name "USB_D+") (class "Default")
      (node (ref "D1") (pin "4") (pinfunction "I/O2_2_4") (pintype "bidirectional"))
      (node (ref "U1") (pin "14") (pinfunction "IO13_14") (pintype "bidirectional"))
    )
    (net (code "51") (name "USB_D-") (class "Default")
      (node (ref "D1") (pin "6") (pinfunction "I/O1_2_6") (pintype "bidirectional"))
      (node (ref "U1") (pin "13") (pinfunction "IO12_13") (pintype "bidirectional"))
    )
    (net (code "52") (name "VBAT") (class "Default")
      (node (ref "C2_BAT") (pin "1") (pinfunction "1_1") (pintype "passive"))
      (node (ref "MCP73831") (pin "3") (pinfunction "VBAT_3") (pintype "power_in"))
      (node (ref "Q1") (pin "3") (pinfunction "D_3") (pintype "bidirectional"))
      (node (ref "U4") (pin "2") (pinfunction "CELL_2") (pintype "power_in"))
      (node (ref "U4") (pin "3") (pinfunction "VDD_3") (pintype "power_in"))
      (node (ref "VBAT") (pin "TP") (pinfunction "TP_TP") (pintype "input"))
    )
    (net (code "53") (name "VBUS") (class "Default")
      (node (ref "C1_BAT") (pin "1") (pinfunction "1_1") (pintype "passive"))
      (node (ref "C4_USB") (pin "1") (pinfunction "1_1") (pintype "passive"))
      (node (ref "C5_USB") (pin "1") (pinfunction "1_1") (pintype "passive"))
      (node (ref "CHG_LED") (pin "A") (pinfunction "A_A") (pintype "passive"))
      (node (ref "D1") (pin "2") (pinfunction "GND_2") (pintype "bidirectional"))
      (node (ref "D2") (pin "2") (pinfunction "ANODE_2") (pintype "bidirectional"))
      (node (ref "MCP73831") (pin "4") (pinfunction "VIN_4") (pintype "power_in"))
      (node (ref "PFMF.050.1") (pin "2") (pinfunction "2_2") (pintype "passive"))
      (node (ref "Q1") (pin "1") (pinfunction "G_1") (pintype "bidirectional"))
      (node (ref "R1_PWRUSB") (pin "2") (pinfunction "2_2") (pintype "passive"))
      (node (ref "VBUS") (pin "TP") (pinfunction "TP_TP") (pintype "input"))
    )
    (net (code "54") (name "VRTC") (class "Default")
      (node (ref "C1") (pin "1") (pinfunction "1_1") (pintype "passive"))
      (node (ref "C10_SUPERCAP") (pin "1") (pinfunction "1_1") (pintype "passive"))
      (node (ref "R_CAPACITOR") (pin "2") (pinfunction "2_2") (pintype "passive"))
      (node (ref "U3") (pin "14") (pinfunction "VBAT_14") (pintype "power_in"))
    )
    (net (code "55") (name "VUSB") (class "Default")
      (node (ref "J2") (pin "A4") (pinfunction "A4_A4") (pintype "bidirectional"))
      (node (ref "J2") (pin "A9") (pinfunction "A9_A9") (pintype "bidirectional"))
      (node (ref "J2") (pin "B4") (pinfunction "B4_B4") (pintype "bidirectional"))
      (node (ref "J2") (pin "B9") (pinfunction "B9_B9") (pintype "bidirectional"))
      (node (ref "PFMF.050.1") (pin "1") (pinfunction "1_1") (pintype "passive"))
    )
    (net (code "56") (name "unconnected-(IC1-NC-Pad4)") (class "Default")
      (node (ref "IC1") (pin "4") (pinfunction "NC_4") (pintype "no_connect"))
    )
    (net (code "57") (name "unconnected-(IC2-NC-Pad4)") (class "Default")
      (node (ref "IC2") (pin "4") (pinfunction "NC_4") (pintype "no_connect"))
    )
    (net (code "58") (name "unconnected-(J1-Pad1)") (class "Default")
      (node (ref "J1") (pin "1") (pinfunction "1_1") (pintype "bidirectional"))
    )
    (net (code "59") (name "unconnected-(J1-Pad6)") (class "Default")
      (node (ref "J1") (pin "6") (pinfunction "6_6") (pintype "bidirectional"))
    )
    (net (code "60") (name "unconnected-(J1-Pad7)") (class "Default")
      (node (ref "J1") (pin "7") (pinfunction "7_7") (pintype "bidirectional"))
    )
    (net (code "61") (name "unconnected-(J2-PadA8)") (class "Default")
      (node (ref "J2") (pin "A8") (pinfunction "A8_A8") (pintype "bidirectional"))
    )
    (net (code "62") (name "unconnected-(J2-PadB8)") (class "Default")
      (node (ref "J2") (pin "B8") (pinfunction "B8_B8") (pintype "bidirectional"))
    )
    (net (code "63") (name "unconnected-(J4-DAT1-PadP8)") (class "Default")
      (node (ref "J4") (pin "P8") (pinfunction "DAT1_P8") (pintype "bidirectional"))
    )
    (net (code "64") (name "unconnected-(J4-DAT2-PadP1)") (class "Default")
      (node (ref "J4") (pin "P1") (pinfunction "DAT2_P1") (pintype "bidirectional"))
    )
    (net (code "65") (name "unconnected-(J4-DETECTION_1-PadS1)") (class "Default")
      (node (ref "J4") (pin "S1") (pinfunction "DETECTION_1_S1") (pintype "bidirectional"))
    )
    (net (code "66") (name "unconnected-(J4-DETECTION_2-PadS2)") (class "Default")
      (node (ref "J4") (pin "S2") (pinfunction "DETECTION_2_S2") (pintype "bidirectional"))
    )
    (net (code "67") (name "unconnected-(U1-NC-Pad22)") (class "Default")
      (node (ref "U1") (pin "22") (pinfunction "NC_22") (pintype "no_connect"))
    )
    (net (code "68") (name "unconnected-(U4-~{ALERT}-Pad5)") (class "Default")
      (node (ref "U4") (pin "5") (pinfunction "~{ALERT}_5") (pintype "output"))
    )
  )
)
